# powersupply.net
KiCad netlist of a schematic drawn in EAGLE
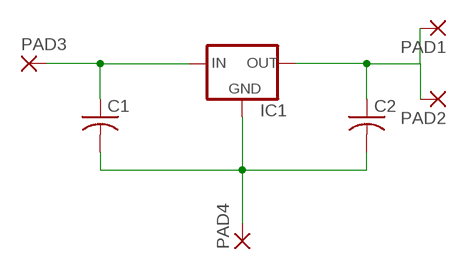
[diagram p0: schematic, sheet 1]

(export (version "E")
  (design (tool "Eeschema 10.0.6"))
  (components
    (comp (ref "C1")
      (value "C-US025-040X050")
      (footprint "eagle-import:C025-040X050")
      (libsource (lib "eagle-import") (part "C-US025-040X050"))
    )
    (comp (ref "C2")
      (value "C-US025-040X050")
      (footprint "eagle-import:C025-040X050")
      (libsource (lib "eagle-import") (part "C-US025-040X050"))
    )
    (comp (ref "IC1")
      (value "78MXXL")
      (footprint "eagle-import:78MXXL")
      (libsource (lib "eagle-import") (part "78MXXL"))
    )
    (comp (ref "PAD1")
      (value "2,54/1,1")
      (footprint "eagle-import:2,54_1,1")
      (libsource (lib "eagle-import") (part "2,54/1,1"))
    )
    (comp (ref "PAD2")
      (value "2,54/1,1")
      (footprint "eagle-import:2,54_1,1")
      (libsource (lib "eagle-import") (part "2,54/1,1"))
    )
    (comp (ref "PAD3")
      (value "2,54/1,1")
      (footprint "eagle-import:2,54_1,1")
      (libsource (lib "eagle-import") (part "2,54/1,1"))
    )
    (comp (ref "PAD4")
      (value "2,54/1,1")
      (footprint "eagle-import:2,54_1,1")
      (libsource (lib "eagle-import") (part "2,54/1,1"))
    )
  )
  (nets
    (net (code "1") (name "Net-(PAD1-P)") (class "Default")
      (node (ref "C2") (pin "1") (pinfunction "1_1") (pintype "passive"))
      (node (ref "IC1") (pin "OUT") (pinfunction "OUT_OUT") (pintype "passive"))
      (node (ref "PAD1") (pin "1") (pinfunction "P_1") (pintype "passive"))
      (node (ref "PAD2") (pin "1") (pinfunction "P_1") (pintype "passive"))
    )
    (net (code "2") (name "Net-(PAD3-P)") (class "Default")
      (node (ref "C1") (pin "1") (pinfunction "1_1") (pintype "passive"))
      (node (ref "IC1") (pin "IN") (pinfunction "IN_IN") (pintype "input"))
      (node (ref "PAD3") (pin "1") (pinfunction "P_1") (pintype "passive"))
    )
    (net (code "3") (name "Net-(PAD4-P)") (class "Default")
      (node (ref "C1") (pin "2") (pinfunction "2_2") (pintype "passive"))
      (node (ref "C2") (pin "2") (pinfunction "2_2") (pintype "passive"))
      (node (ref "IC1") (pin "GND") (pinfunction "GND_GND") (pintype "input"))
      (node (ref "PAD4") (pin "1") (pinfunction "P_1") (pintype "passive"))
    )
  )
)
